# 3_5G.net
KiCad netlist of a schematic drawn in Altium Designer
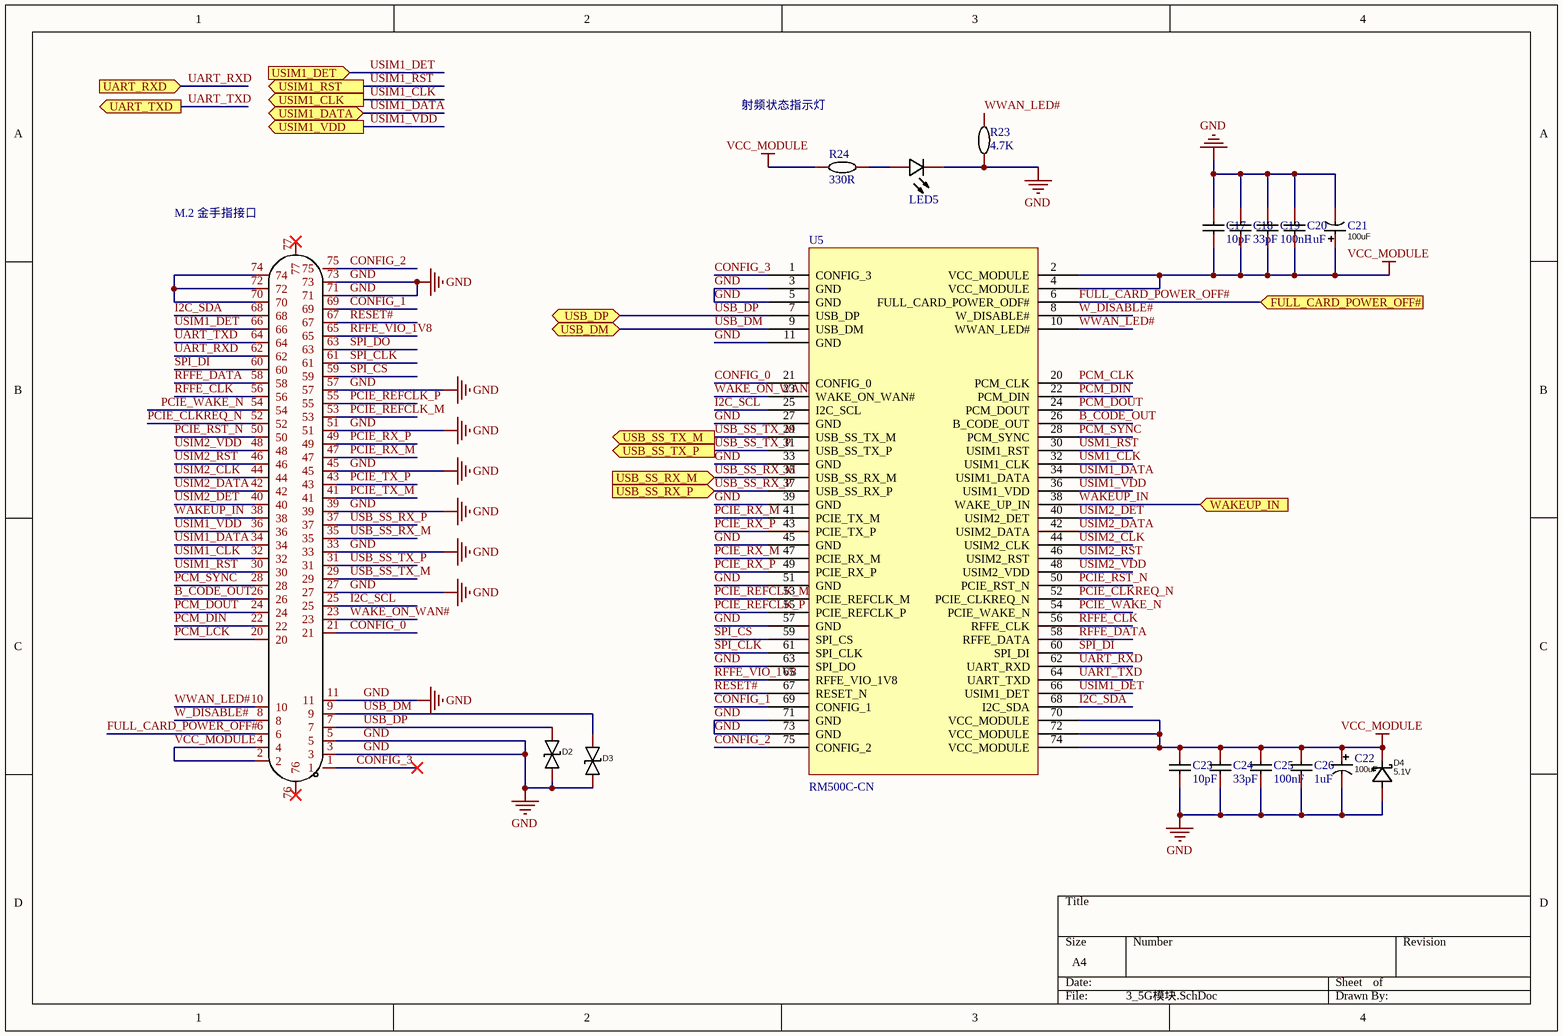
[diagram p0: 3_5G模块.SchDoc]

(export (version "E")
  (design (tool "Eeschema 10.0.6"))
  (components
    (comp (ref "C17")
      (value "100nF")
      (footprint "0603C")
      (fields
        (field (name "MANUFACTURER") "FH")
        (field (name "MANUFACTURER PART") "0603B104K500NT")
        (field (name "NAME") "10pF")
      )
      (libsource (lib "3_C5157152_TP5000移动电源方案验证板.schdoc") (part "0603B104K500NT"))
    )
    (comp (ref "C18")
      (value "100nF")
      (footprint "0603C")
      (fields
        (field (name "MANUFACTURER") "FH")
        (field (name "MANUFACTURER PART") "0603B104K500NT")
        (field (name "NAME") "33pF")
      )
      (libsource (lib "3_C5157152_TP5000移动电源方案验证板.schdoc") (part "0603B104K500NT"))
    )
    (comp (ref "C19")
      (value "100nF")
      (footprint "0603C")
      (fields
        (field (name "MANUFACTURER") "FH")
        (field (name "MANUFACTURER PART") "0603B104K500NT")
        (field (name "NAME") "100nF")
      )
      (libsource (lib "3_C5157152_TP5000移动电源方案验证板.schdoc") (part "0603B104K500NT"))
    )
    (comp (ref "C20")
      (value "100nF")
      (footprint "0603C")
      (fields
        (field (name "MANUFACTURER") "FH")
        (field (name "MANUFACTURER PART") "0603B104K500NT")
        (field (name "NAME") "1uF")
      )
      (libsource (lib "3_C5157152_TP5000移动电源方案验证板.schdoc") (part "0603B104K500NT"))
    )
    (comp (ref "C21")
      (value "100uF")
      (footprint "1206C")
      (fields (field (name "MANUFACTURER PART") "CL31A226KAHNNNE"))
      (libsource (lib "3_C5157152_TP5000移动电源方案验证板.schdoc") (part "CL31A226KAHNNNE"))
    )
    (comp (ref "C22")
      (value "100uF")
      (footprint "1206C")
      (fields (field (name "MANUFACTURER PART") "CL31A226KAHNNNE"))
      (libsource (lib "3_C5157152_TP5000移动电源方案验证板.schdoc") (part "CL31A226KAHNNNE"))
    )
    (comp (ref "C23")
      (value "100nF")
      (footprint "0603C")
      (fields
        (field (name "MANUFACTURER") "FH")
        (field (name "MANUFACTURER PART") "0603B104K500NT")
        (field (name "NAME") "10pF")
      )
      (libsource (lib "3_C5157152_TP5000移动电源方案验证板.schdoc") (part "0603B104K500NT"))
    )
    (comp (ref "C24")
      (value "100nF")
      (footprint "0603C")
      (fields
        (field (name "MANUFACTURER") "FH")
        (field (name "MANUFACTURER PART") "0603B104K500NT")
        (field (name "NAME") "33pF")
      )
      (libsource (lib "3_C5157152_TP5000移动电源方案验证板.schdoc") (part "0603B104K500NT"))
    )
    (comp (ref "C25")
      (value "100nF")
      (footprint "0603C")
      (fields
        (field (name "MANUFACTURER") "FH")
        (field (name "MANUFACTURER PART") "0603B104K500NT")
        (field (name "NAME") "100nF")
      )
      (libsource (lib "3_C5157152_TP5000移动电源方案验证板.schdoc") (part "0603B104K500NT"))
    )
    (comp (ref "C26")
      (value "100nF")
      (footprint "0603C")
      (fields
        (field (name "MANUFACTURER") "FH")
        (field (name "MANUFACTURER PART") "0603B104K500NT")
        (field (name "NAME") "1uF")
      )
      (libsource (lib "3_C5157152_TP5000移动电源方案验证板.schdoc") (part "0603B104K500NT"))
    )
    (comp (ref "CN3")
      (value "APCI0078-P002A_C7498136")
      (footprint "NGFF-SMD_APCI0078-P002A")
      (fields (field (name "MANUFACTURER PART") "APCI0078-P002A"))
      (libsource (lib "APCI0078-P002A_C74981361_APCI0078-P002A_C7498136.schdoc") (part "APCI0078-P002A_C7498136"))
    )
    (comp (ref "D2")
      (value "PESD3V3L1BA-N")
      (footprint "SOD-323_L1.8-W1.3-LS2.5-BI")
      (libsource (lib "PESD3V3L1BA-N1_PESD3V3L1BA-N.schdoc") (part "PESD3V3L1BA-N"))
    )
    (comp (ref "D3")
      (value "PESD3V3L1BA-N")
      (footprint "SOD-323_L1.8-W1.3-LS2.5-BI")
      (libsource (lib "PESD3V3L1BA-N1_PESD3V3L1BA-N.schdoc") (part "PESD3V3L1BA-N"))
    )
    (comp (ref "D4")
      (value "SMF75A_C5116416")
      (footprint "SOD-123FL_L2.8-W1.8-LS3.7-RD")
      (fields
        (field (name "MANUFACTURER PART") "SMF75A")
        (field (name "REVERSE STAND-OFF VOLTAGE (VRWM)") "5.1V")
      )
      (libsource (lib "SMF75A_C51164161_SMF75A_C5116416.schdoc") (part "SMF75A_C5116416"))
    )
    (comp (ref "LED5")
      (value "NCD0603G1")
      (footprint "LED0603-RD")
      (libsource (lib "3_C5157152_TP5000移动电源方案验证板.schdoc") (part "NCD0603G1"))
    )
    (comp (ref "R23")
      (value "4.7K")
      (footprint "0603R")
      (fields
        (field (name "MANUFACTURER") "Tyohm")
        (field (name "MANUFACTURER PART") "RMC06034.7k5%N")
        (field (name "NAME") "4.7K")
      )
      (libsource (lib "3_C5157152_TP5000移动电源方案验证板.schdoc") (part "RMC06034.7k5%N"))
    )
    (comp (ref "R24")
      (value "330R")
      (footprint "0402R")
      (fields (field (name "MANUFACTURER PART") "0402WGF1001TCE"))
      (libsource (lib "3_C5157152_TP5000移动电源方案验证板.schdoc") (part "0402WGF1001TCE"))
    )
    (comp (ref "U5") (value "RM500C-CN") (libsource (lib "5G_Module") (part "RM500C")))
  )
  (nets
    (net (code "1") (name "/B_CODE_OUT") (class "Default")
      (node (ref "CN3") (pin "26") (pinfunction "26_26") (pintype "passive"))
      (node (ref "U5") (pin "26") (pinfunction "B_CODE_OUT_26") (pintype "passive"))
    )
    (net (code "2") (name "/CONFIG_0") (class "Default")
      (node (ref "CN3") (pin "21") (pinfunction "21_21") (pintype "passive"))
      (node (ref "U5") (pin "21") (pinfunction "CONFIG_0_21") (pintype "passive"))
    )
    (net (code "3") (name "/CONFIG_1") (class "Default")
      (node (ref "CN3") (pin "69") (pinfunction "69_69") (pintype "passive"))
      (node (ref "U5") (pin "69") (pinfunction "CONFIG_1_69") (pintype "passive"))
    )
    (net (code "4") (name "/CONFIG_2") (class "Default")
      (node (ref "CN3") (pin "75") (pinfunction "75_75") (pintype "passive"))
      (node (ref "U5") (pin "75") (pinfunction "CONFIG_2_75") (pintype "passive"))
    )
    (net (code "5") (name "/CONFIG_3") (class "Default")
      (node (ref "CN3") (pin "1") (pinfunction "1_1") (pintype "passive"))
      (node (ref "U5") (pin "1") (pinfunction "CONFIG_3_1") (pintype "passive"))
    )
    (net (code "6") (name "/FULL_CARD_POWER_OFF#") (class "Default")
      (node (ref "CN3") (pin "6") (pinfunction "6_6") (pintype "passive"))
      (node (ref "U5") (pin "6") (pinfunction "FULL_CARD_POWER_ODF#_6") (pintype "passive"))
    )
    (net (code "7") (name "/I2C_SCL") (class "Default")
      (node (ref "CN3") (pin "25") (pinfunction "25_25") (pintype "passive"))
      (node (ref "U5") (pin "25") (pinfunction "I2C_SCL_25") (pintype "passive"))
    )
    (net (code "8") (name "/I2C_SDA") (class "Default")
      (node (ref "CN3") (pin "68") (pinfunction "68_68") (pintype "passive"))
      (node (ref "U5") (pin "68") (pinfunction "I2C_SDA_68") (pintype "passive"))
    )
    (net (code "9") (name "/PCIE_CLKREQ_N") (class "Default")
      (node (ref "CN3") (pin "52") (pinfunction "52_52") (pintype "passive"))
      (node (ref "U5") (pin "52") (pinfunction "PCIE_CLKREQ_N_52") (pintype "passive"))
    )
    (net (code "10") (name "/PCIE_REFCLK_M") (class "Default")
      (node (ref "CN3") (pin "53") (pinfunction "53_53") (pintype "passive"))
      (node (ref "U5") (pin "53") (pinfunction "PCIE_REFCLK_M_53") (pintype "passive"))
    )
    (net (code "11") (name "/PCIE_REFCLK_P") (class "Default")
      (node (ref "CN3") (pin "55") (pinfunction "55_55") (pintype "passive"))
      (node (ref "U5") (pin "55") (pinfunction "PCIE_REFCLK_P_55") (pintype "passive"))
    )
    (net (code "12") (name "/PCIE_RST_N") (class "Default")
      (node (ref "CN3") (pin "50") (pinfunction "50_50") (pintype "passive"))
      (node (ref "U5") (pin "50") (pinfunction "PCIE_RST_N_50") (pintype "passive"))
    )
    (net (code "13") (name "/PCIE_RX_M") (class "Default")
      (node (ref "CN3") (pin "47") (pinfunction "47_47") (pintype "passive"))
      (node (ref "U5") (pin "41") (pinfunction "PCIE_TX_M_41") (pintype "passive"))
      (node (ref "U5") (pin "47") (pinfunction "PCIE_RX_M_47") (pintype "passive"))
    )
    (net (code "14") (name "/PCIE_RX_P") (class "Default")
      (node (ref "CN3") (pin "49") (pinfunction "49_49") (pintype "passive"))
      (node (ref "U5") (pin "43") (pinfunction "PCIE_TX_P_43") (pintype "passive"))
      (node (ref "U5") (pin "49") (pinfunction "PCIE_RX_P_49") (pintype "passive"))
    )
    (net (code "15") (name "/PCIE_TX_M") (class "Default")
      (node (ref "CN3") (pin "41") (pinfunction "41_41") (pintype "passive"))
    )
    (net (code "16") (name "/PCIE_TX_P") (class "Default")
      (node (ref "CN3") (pin "43") (pinfunction "43_43") (pintype "passive"))
    )
    (net (code "17") (name "/PCIE_WAKE_N") (class "Default")
      (node (ref "CN3") (pin "54") (pinfunction "54_54") (pintype "passive"))
      (node (ref "U5") (pin "54") (pinfunction "PCIE_WAKE_N_54") (pintype "passive"))
    )
    (net (code "18") (name "/PCM_CLK") (class "Default")
      (node (ref "U5") (pin "20") (pinfunction "PCM_CLK_20") (pintype "passive"))
    )
    (net (code "19") (name "/PCM_DIN") (class "Default")
      (node (ref "CN3") (pin "22") (pinfunction "22_22") (pintype "passive"))
      (node (ref "U5") (pin "22") (pinfunction "PCM_DIN_22") (pintype "passive"))
    )
    (net (code "20") (name "/PCM_DOUT") (class "Default")
      (node (ref "CN3") (pin "24") (pinfunction "24_24") (pintype "passive"))
      (node (ref "U5") (pin "24") (pinfunction "PCM_DOUT_24") (pintype "passive"))
    )
    (net (code "21") (name "/PCM_LCK") (class "Default")
      (node (ref "CN3") (pin "20") (pinfunction "20_20") (pintype "passive"))
    )
    (net (code "22") (name "/PCM_SYNC") (class "Default")
      (node (ref "CN3") (pin "28") (pinfunction "28_28") (pintype "passive"))
      (node (ref "U5") (pin "28") (pinfunction "PCM_SYNC_28") (pintype "passive"))
    )
    (net (code "23") (name "/RESET#") (class "Default")
      (node (ref "CN3") (pin "67") (pinfunction "67_67") (pintype "passive"))
      (node (ref "U5") (pin "67") (pinfunction "RESET_N_67") (pintype "passive"))
    )
    (net (code "24") (name "/RFFE_CLK") (class "Default")
      (node (ref "CN3") (pin "56") (pinfunction "56_56") (pintype "passive"))
      (node (ref "U5") (pin "56") (pinfunction "RFFE_CLK_56") (pintype "passive"))
    )
    (net (code "25") (name "/RFFE_DATA") (class "Default")
      (node (ref "CN3") (pin "58") (pinfunction "58_58") (pintype "passive"))
      (node (ref "U5") (pin "58") (pinfunction "RFFE_DATA_58") (pintype "passive"))
    )
    (net (code "26") (name "/RFFE_VIO_1V8") (class "Default")
      (node (ref "CN3") (pin "65") (pinfunction "65_65") (pintype "passive"))
      (node (ref "U5") (pin "65") (pinfunction "RFFE_VIO_1V8_65") (pintype "passive"))
    )
    (net (code "27") (name "/SPI_CLK") (class "Default")
      (node (ref "CN3") (pin "61") (pinfunction "61_61") (pintype "passive"))
      (node (ref "U5") (pin "61") (pinfunction "SPI_CLK_61") (pintype "passive"))
    )
    (net (code "28") (name "/SPI_CS") (class "Default")
      (node (ref "CN3") (pin "59") (pinfunction "59_59") (pintype "passive"))
      (node (ref "U5") (pin "59") (pinfunction "SPI_CS_59") (pintype "passive"))
    )
    (net (code "29") (name "/SPI_DI") (class "Default")
      (node (ref "CN3") (pin "60") (pinfunction "60_60") (pintype "passive"))
      (node (ref "U5") (pin "60") (pinfunction "SPI_DI_60") (pintype "passive"))
    )
    (net (code "30") (name "/SPI_DO") (class "Default")
      (node (ref "CN3") (pin "63") (pinfunction "63_63") (pintype "passive"))
    )
    (net (code "31") (name "/UART_RXD") (class "Default")
      (node (ref "CN3") (pin "62") (pinfunction "62_62") (pintype "passive"))
      (node (ref "U5") (pin "62") (pinfunction "UART_RXD_62") (pintype "passive"))
    )
    (net (code "32") (name "/UART_TXD") (class "Default")
      (node (ref "CN3") (pin "64") (pinfunction "64_64") (pintype "passive"))
      (node (ref "U5") (pin "64") (pinfunction "UART_TXD_64") (pintype "passive"))
    )
    (net (code "33") (name "/USB_DM") (class "Default")
      (node (ref "CN3") (pin "9") (pinfunction "9_9") (pintype "passive"))
      (node (ref "D3") (pin "2") (pinfunction "2_2") (pintype "passive"))
      (node (ref "U5") (pin "9") (pinfunction "USB_DM_9") (pintype "passive"))
    )
    (net (code "34") (name "/USB_DP") (class "Default")
      (node (ref "CN3") (pin "7") (pinfunction "7_7") (pintype "passive"))
      (node (ref "D2") (pin "2") (pinfunction "2_2") (pintype "passive"))
      (node (ref "U5") (pin "7") (pinfunction "USB_DP_7") (pintype "passive"))
    )
    (net (code "35") (name "/USB_SS_RX_M") (class "Default")
      (node (ref "CN3") (pin "35") (pinfunction "35_35") (pintype "passive"))
      (node (ref "U5") (pin "35") (pinfunction "USB_SS_RX_M_35") (pintype "passive"))
    )
    (net (code "36") (name "/USB_SS_RX_P") (class "Default")
      (node (ref "CN3") (pin "37") (pinfunction "37_37") (pintype "passive"))
      (node (ref "U5") (pin "37") (pinfunction "USB_SS_RX_P_37") (pintype "passive"))
    )
    (net (code "37") (name "/USB_SS_TX_M") (class "Default")
      (node (ref "CN3") (pin "29") (pinfunction "29_29") (pintype "passive"))
      (node (ref "U5") (pin "29") (pinfunction "USB_SS_TX_M_29") (pintype "passive"))
    )
    (net (code "38") (name "/USB_SS_TX_P") (class "Default")
      (node (ref "CN3") (pin "31") (pinfunction "31_31") (pintype "passive"))
      (node (ref "U5") (pin "31") (pinfunction "USB_SS_TX_P_31") (pintype "passive"))
    )
    (net (code "39") (name "/USIM1_CLK") (class "Default")
      (node (ref "CN3") (pin "32") (pinfunction "32_32") (pintype "passive"))
    )
    (net (code "40") (name "/USIM1_DATA") (class "Default")
      (node (ref "CN3") (pin "34") (pinfunction "34_34") (pintype "passive"))
      (node (ref "U5") (pin "34") (pinfunction "USIM1_DATA_34") (pintype "passive"))
    )
    (net (code "41") (name "/USIM1_DET") (class "Default")
      (node (ref "CN3") (pin "66") (pinfunction "66_66") (pintype "passive"))
      (node (ref "U5") (pin "66") (pinfunction "USIM1_DET_66") (pintype "passive"))
    )
    (net (code "42") (name "/USIM1_RST") (class "Default")
      (node (ref "CN3") (pin "30") (pinfunction "30_30") (pintype "passive"))
    )
    (net (code "43") (name "/USIM1_VDD") (class "Default")
      (node (ref "CN3") (pin "36") (pinfunction "36_36") (pintype "passive"))
      (node (ref "U5") (pin "36") (pinfunction "USIM1_VDD_36") (pintype "passive"))
    )
    (net (code "44") (name "/USIM2_CLK") (class "Default")
      (node (ref "CN3") (pin "44") (pinfunction "44_44") (pintype "passive"))
      (node (ref "U5") (pin "44") (pinfunction "USIM2_CLK_44") (pintype "passive"))
    )
    (net (code "45") (name "/USIM2_DATA") (class "Default")
      (node (ref "CN3") (pin "42") (pinfunction "42_42") (pintype "passive"))
      (node (ref "U5") (pin "42") (pinfunction "USIM2_DATA_42") (pintype "passive"))
    )
    (net (code "46") (name "/USIM2_DET") (class "Default")
      (node (ref "CN3") (pin "40") (pinfunction "40_40") (pintype "passive"))
      (node (ref "U5") (pin "40") (pinfunction "USIM2_DET_40") (pintype "passive"))
    )
    (net (code "47") (name "/USIM2_RST") (class "Default")
      (node (ref "CN3") (pin "46") (pinfunction "46_46") (pintype "passive"))
      (node (ref "U5") (pin "46") (pinfunction "USIM2_RST_46") (pintype "passive"))
    )
    (net (code "48") (name "/USIM2_VDD") (class "Default")
      (node (ref "CN3") (pin "48") (pinfunction "48_48") (pintype "passive"))
      (node (ref "U5") (pin "48") (pinfunction "USIM2_VDD_48") (pintype "passive"))
    )
    (net (code "49") (name "/USM1_CLK") (class "Default")
      (node (ref "U5") (pin "32") (pinfunction "USIM1_CLK_32") (pintype "passive"))
    )
    (net (code "50") (name "/USM1_RST") (class "Default")
      (node (ref "U5") (pin "30") (pinfunction "USIM1_RST_30") (pintype "passive"))
    )
    (net (code "51") (name "/WAKEUP_IN") (class "Default")
      (node (ref "CN3") (pin "38") (pinfunction "38_38") (pintype "passive"))
      (node (ref "U5") (pin "38") (pinfunction "WAKE_UP_IN_38") (pintype "passive"))
    )
    (net (code "52") (name "/WAKE_ON_WAN#") (class "Default")
      (node (ref "CN3") (pin "23") (pinfunction "23_23") (pintype "passive"))
      (node (ref "U5") (pin "23") (pinfunction "WAKE_ON_WAN#_23") (pintype "passive"))
    )
    (net (code "53") (name "/WWAN_LED#") (class "Default")
      (node (ref "CN3") (pin "10") (pinfunction "10_10") (pintype "passive"))
      (node (ref "R23") (pin "2") (pinfunction "2_2") (pintype "passive"))
      (node (ref "U5") (pin "10") (pinfunction "WWAN_LED#_10") (pintype "passive"))
    )
    (net (code "54") (name "/W_DISABLE#") (class "Default")
      (node (ref "CN3") (pin "8") (pinfunction "8_8") (pintype "passive"))
      (node (ref "U5") (pin "8") (pinfunction "W_DISABLE#_8") (pintype "passive"))
    )
    (net (code "55") (name "GND") (class "Default")
      (node (ref "C17") (pin "1") (pinfunction "1_1") (pintype "passive"))
      (node (ref "C18") (pin "1") (pinfunction "1_1") (pintype "passive"))
      (node (ref "C19") (pin "1") (pinfunction "1_1") (pintype "passive"))
      (node (ref "C20") (pin "1") (pinfunction "1_1") (pintype "passive"))
      (node (ref "C21") (pin "2") (pinfunction "2_2") (pintype "passive"))
      (node (ref "C22") (pin "2") (pinfunction "2_2") (pintype "passive"))
      (node (ref "C23") (pin "1") (pinfunction "1_1") (pintype "passive"))
      (node (ref "C24") (pin "1") (pinfunction "1_1") (pintype "passive"))
      (node (ref "C25") (pin "1") (pinfunction "1_1") (pintype "passive"))
      (node (ref "C26") (pin "1") (pinfunction "1_1") (pintype "passive"))
      (node (ref "CN3") (pin "11") (pinfunction "11_11") (pintype "passive"))
      (node (ref "CN3") (pin "27") (pinfunction "27_27") (pintype "passive"))
      (node (ref "CN3") (pin "3") (pinfunction "3_3") (pintype "passive"))
      (node (ref "CN3") (pin "33") (pinfunction "33_33") (pintype "passive"))
      (node (ref "CN3") (pin "39") (pinfunction "39_39") (pintype "passive"))
      (node (ref "CN3") (pin "45") (pinfunction "45_45") (pintype "passive"))
      (node (ref "CN3") (pin "5") (pinfunction "5_5") (pintype "passive"))
      (node (ref "CN3") (pin "51") (pinfunction "51_51") (pintype "passive"))
      (node (ref "CN3") (pin "57") (pinfunction "57_57") (pintype "passive"))
      (node (ref "CN3") (pin "71") (pinfunction "71_71") (pintype "passive"))
      (node (ref "CN3") (pin "73") (pinfunction "73_73") (pintype "passive"))
      (node (ref "D2") (pin "1") (pinfunction "1_1") (pintype "passive"))
      (node (ref "D3") (pin "1") (pinfunction "1_1") (pintype "passive"))
      (node (ref "D4") (pin "2") (pinfunction "A_2") (pintype "passive"))
      (node (ref "LED5") (pin "1") (pinfunction "C_1") (pintype "passive"))
      (node (ref "R23") (pin "1") (pinfunction "1_1") (pintype "passive"))
      (node (ref "U5") (pin "11") (pinfunction "GND_11") (pintype "passive"))
      (node (ref "U5") (pin "27") (pinfunction "GND_27") (pintype "passive"))
      (node (ref "U5") (pin "3") (pinfunction "GND_3") (pintype "passive"))
      (node (ref "U5") (pin "33") (pinfunction "GND_33") (pintype "passive"))
      (node (ref "U5") (pin "39") (pinfunction "GND_39") (pintype "passive"))
      (node (ref "U5") (pin "45") (pinfunction "GND_45") (pintype "passive"))
      (node (ref "U5") (pin "5") (pinfunction "GND_5") (pintype "passive"))
      (node (ref "U5") (pin "51") (pinfunction "GND_51") (pintype "passive"))
      (node (ref "U5") (pin "57") (pinfunction "GND_57") (pintype "passive"))
      (node (ref "U5") (pin "63") (pinfunction "SPI_DO_63") (pintype "passive"))
      (node (ref "U5") (pin "71") (pinfunction "GND_71") (pintype "passive"))
      (node (ref "U5") (pin "73") (pinfunction "GND_73") (pintype "passive"))
    )
    (net (code "56") (name "Net-(CN3-Pad70)") (class "Default")
      (node (ref "CN3") (pin "70") (pinfunction "70_70") (pintype "passive"))
      (node (ref "CN3") (pin "72") (pinfunction "72_72") (pintype "passive"))
      (node (ref "CN3") (pin "74") (pinfunction "74_74") (pintype "passive"))
    )
    (net (code "57") (name "Net-(LED5-A)") (class "Default")
      (node (ref "LED5") (pin "2") (pinfunction "A_2") (pintype "passive"))
      (node (ref "R24") (pin "2") (pinfunction "2_2") (pintype "passive"))
    )
    (net (code "58") (name "VCC_MODULE") (class "Default")
      (node (ref "C17") (pin "2") (pinfunction "2_2") (pintype "passive"))
      (node (ref "C18") (pin "2") (pinfunction "2_2") (pintype "passive"))
      (node (ref "C19") (pin "2") (pinfunction "2_2") (pintype "passive"))
      (node (ref "C20") (pin "2") (pinfunction "2_2") (pintype "passive"))
      (node (ref "C21") (pin "1") (pinfunction "1_1") (pintype "passive"))
      (node (ref "C22") (pin "1") (pinfunction "1_1") (pintype "passive"))
      (node (ref "C23") (pin "2") (pinfunction "2_2") (pintype "passive"))
      (node (ref "C24") (pin "2") (pinfunction "2_2") (pintype "passive"))
      (node (ref "C25") (pin "2") (pinfunction "2_2") (pintype "passive"))
      (node (ref "C26") (pin "2") (pinfunction "2_2") (pintype "passive"))
      (node (ref "CN3") (pin "2") (pinfunction "2_2") (pintype "passive"))
      (node (ref "CN3") (pin "4") (pinfunction "4_4") (pintype "passive"))
      (node (ref "D4") (pin "1") (pinfunction "K_1") (pintype "passive"))
      (node (ref "R24") (pin "1") (pinfunction "1_1") (pintype "passive"))
      (node (ref "U5") (pin "2") (pinfunction "VCC_MODULE_2") (pintype "passive"))
      (node (ref "U5") (pin "4") (pinfunction "VCC_MODULE_4") (pintype "passive"))
      (node (ref "U5") (pin "70") (pinfunction "VCC_MODULE_70") (pintype "passive"))
      (node (ref "U5") (pin "72") (pinfunction "VCC_MODULE_72") (pintype "passive"))
      (node (ref "U5") (pin "74") (pinfunction "VCC_MODULE_74") (pintype "passive"))
    )
    (net (code "59") (name "unconnected-(CN3-Pad76)") (class "Default")
      (node (ref "CN3") (pin "76") (pinfunction "76_76") (pintype "passive+no_connect"))
    )
    (net (code "60") (name "unconnected-(CN3-Pad77)") (class "Default")
      (node (ref "CN3") (pin "77") (pinfunction "77_77") (pintype "passive+no_connect"))
    )
  )
)
